# interface_visual.net
KiCad netlist of a schematic drawn in EAGLE
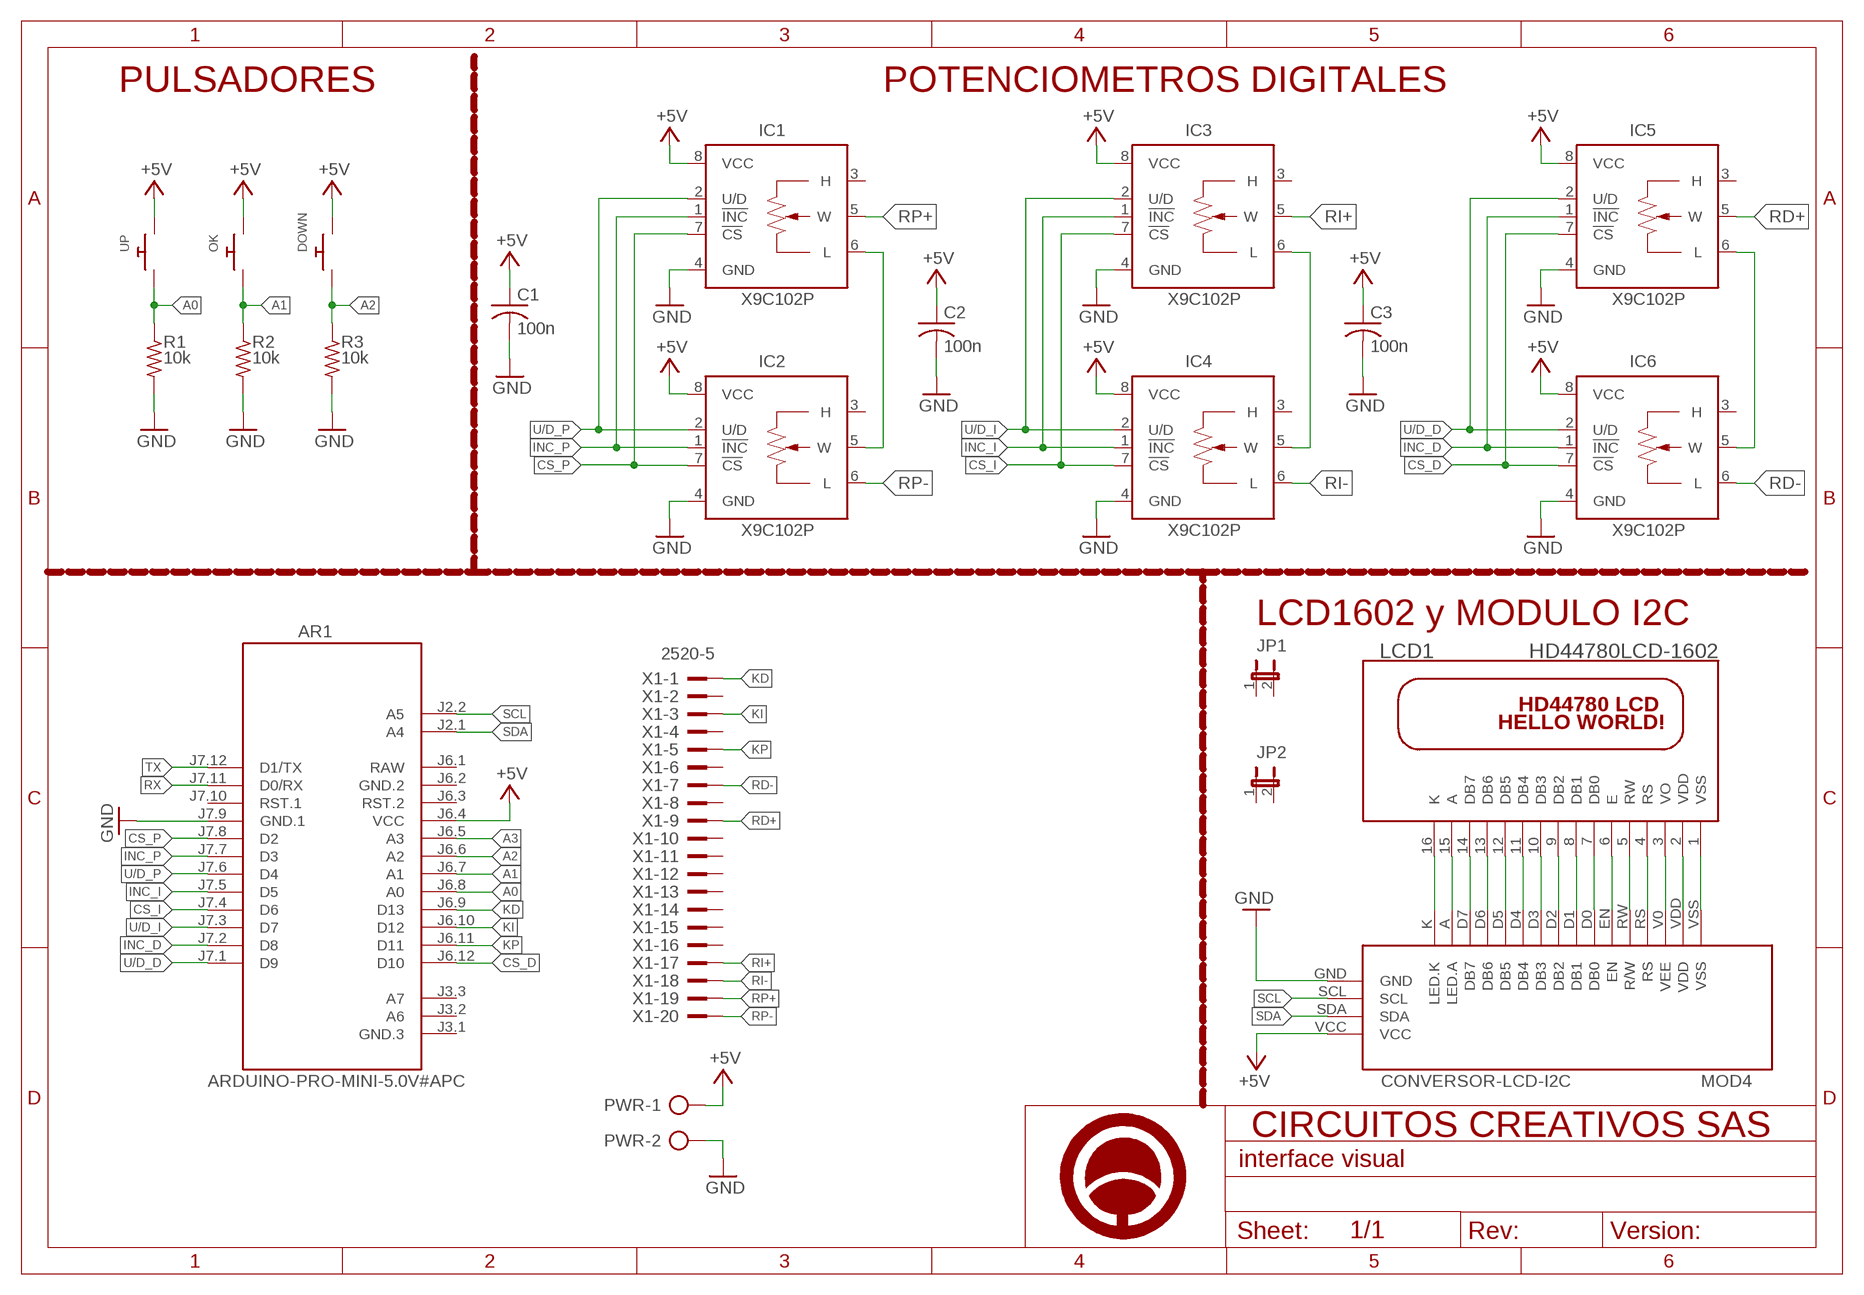
[diagram p0: schematic, sheet 1]

(export (version "E")
  (design (tool "Eeschema 10.0.6"))
  (components
    (comp (ref "AR1")
      (value "ARDUINO-PRO-MINI-5.0V#APC")
      (footprint "eagle-import:ARDUINO-PRO-MINI#APC")
      (libsource (lib "eagle-import") (part "ARDUINO-PRO-MINI-#APC5.0V"))
    )
    (comp (ref "C1")
      (value "100n")
      (footprint "eagle-import:C025-025X050")
      (libsource (lib "eagle-import") (part "C-US025-025X050"))
    )
    (comp (ref "C2")
      (value "100n")
      (footprint "eagle-import:C025-025X050")
      (libsource (lib "eagle-import") (part "C-US025-025X050"))
    )
    (comp (ref "C3")
      (value "100n")
      (footprint "eagle-import:C025-025X050")
      (libsource (lib "eagle-import") (part "C-US025-025X050"))
    )
    (comp (ref "DOWN")
      (value "SWITCH_PUSHBUTTONEVQ-PE")
      (footprint "eagle-import:TACT_PANA-EVQ")
      (libsource (lib "eagle-import") (part "SWITCH_PUSHBUTTONEVQ-PE"))
    )
    (comp (ref "IC1")
      (value "X9C102P")
      (footprint "eagle-import:DIL08")
      (fields (field (name "MF") "INTERSIL"))
      (libsource (lib "eagle-import") (part "X9C102P"))
    )
    (comp (ref "IC2")
      (value "X9C102P")
      (footprint "eagle-import:DIL08")
      (fields (field (name "MF") "INTERSIL"))
      (libsource (lib "eagle-import") (part "X9C102P"))
    )
    (comp (ref "IC3")
      (value "X9C102P")
      (footprint "eagle-import:DIL08")
      (fields (field (name "MF") "INTERSIL"))
      (libsource (lib "eagle-import") (part "X9C102P"))
    )
    (comp (ref "IC4")
      (value "X9C102P")
      (footprint "eagle-import:DIL08")
      (fields (field (name "MF") "INTERSIL"))
      (libsource (lib "eagle-import") (part "X9C102P"))
    )
    (comp (ref "IC5")
      (value "X9C102P")
      (footprint "eagle-import:DIL08")
      (fields (field (name "MF") "INTERSIL"))
      (libsource (lib "eagle-import") (part "X9C102P"))
    )
    (comp (ref "IC6")
      (value "X9C102P")
      (footprint "eagle-import:DIL08")
      (fields (field (name "MF") "INTERSIL"))
      (libsource (lib "eagle-import") (part "X9C102P"))
    )
    (comp (ref "JP1")
      (value "JP1E")
      (footprint "eagle-import:JP1")
      (libsource (lib "eagle-import") (part "JP1E"))
    )
    (comp (ref "JP2")
      (value "JP1E")
      (footprint "eagle-import:JP1")
      (libsource (lib "eagle-import") (part "JP1E"))
    )
    (comp (ref "LCD1")
      (value "HD44780LCD-1602")
      (footprint "eagle-import:LCD1602")
      (libsource (lib "eagle-import") (part "HD44780LCD-1602"))
    )
    (comp (ref "MOD4")
      (value "CONVERSOR-LCD-I2C")
      (footprint "eagle-import:CONVERSOR-LCD-I2C")
      (libsource (lib "eagle-import") (part "CONVERSOR-LCD-I2C"))
    )
    (comp (ref "OK")
      (value "SWITCH_PUSHBUTTONEVQ-PE")
      (footprint "eagle-import:TACT_PANA-EVQ")
      (libsource (lib "eagle-import") (part "SWITCH_PUSHBUTTONEVQ-PE"))
    )
    (comp (ref "PWR")
      (value "AK500/2")
      (footprint "eagle-import:AK500_2")
      (libsource (lib "eagle-import") (part "AK500/2"))
    )
    (comp (ref "R1")
      (value "10k")
      (footprint "eagle-import:0204_7")
      (libsource (lib "eagle-import") (part "R-US_0204/7"))
    )
    (comp (ref "R2")
      (value "10k")
      (footprint "eagle-import:0204_7")
      (libsource (lib "eagle-import") (part "R-US_0204/7"))
    )
    (comp (ref "R3")
      (value "10k")
      (footprint "eagle-import:0204_7")
      (libsource (lib "eagle-import") (part "R-US_0204/7"))
    )
    (comp (ref "U$1")
      (value "A4_HORIZONTAL")
      (footprint "eagle-import:LOGO")
      (libsource (lib "eagle-import") (part "A4_HORIZONTAL"))
    )
    (comp (ref "UP")
      (value "SWITCH_PUSHBUTTONEVQ-PE")
      (footprint "eagle-import:TACT_PANA-EVQ")
      (libsource (lib "eagle-import") (part "SWITCH_PUSHBUTTONEVQ-PE"))
    )
    (comp (ref "X1")
      (value "2520-5")
      (footprint "eagle-import:PAK100_2500-5-20")
      (fields (field (name "MPN") "D2520-5002-AR"))
      (libsource (lib "eagle-import") (part "2520-5"))
    )
  )
  (nets
    (net (code "1") (name "+5V") (class "Default")
      (node (ref "AR1") (pin "J6.4") (pinfunction "VCC_J6.4") (pintype "power_in"))
      (node (ref "C1") (pin "1") (pinfunction "1_1") (pintype "passive"))
      (node (ref "C2") (pin "1") (pinfunction "1_1") (pintype "passive"))
      (node (ref "C3") (pin "1") (pinfunction "1_1") (pintype "passive"))
      (node (ref "DOWN") (pin "P$2") (pinfunction "P$2_P$2") (pintype "passive"))
      (node (ref "IC1") (pin "8") (pinfunction "VCC_8") (pintype "power_in"))
      (node (ref "IC2") (pin "8") (pinfunction "VCC_8") (pintype "power_in"))
      (node (ref "IC3") (pin "8") (pinfunction "VCC_8") (pintype "power_in"))
      (node (ref "IC4") (pin "8") (pinfunction "VCC_8") (pintype "power_in"))
      (node (ref "IC5") (pin "8") (pinfunction "VCC_8") (pintype "power_in"))
      (node (ref "IC6") (pin "8") (pinfunction "VCC_8") (pintype "power_in"))
      (node (ref "MOD4") (pin "VCC") (pinfunction "VCC_VCC") (pintype "power_in"))
      (node (ref "OK") (pin "P$2") (pinfunction "P$2_P$2") (pintype "passive"))
      (node (ref "PWR") (pin "1") (pinfunction "KL_1") (pintype "passive"))
      (node (ref "UP") (pin "P$2") (pinfunction "P$2_P$2") (pintype "passive"))
    )
    (net (code "2") (name "/GND.2") (class "Default")
      (node (ref "AR1") (pin "J6.2") (pinfunction "GND.2_J6.2") (pintype "power_in"))
    )
    (net (code "3") (name "/RAW") (class "Default")
      (node (ref "AR1") (pin "J6.1") (pinfunction "RAW_J6.1") (pintype "power_in"))
    )
    (net (code "4") (name "A0") (class "Default")
      (node (ref "AR1") (pin "J6.8") (pinfunction "A0_J6.8") (pintype "bidirectional"))
      (node (ref "R1") (pin "1") (pinfunction "1_1") (pintype "passive"))
      (node (ref "UP") (pin "P$1") (pinfunction "P$1_P$1") (pintype "passive"))
    )
    (net (code "5") (name "A1") (class "Default")
      (node (ref "AR1") (pin "J6.7") (pinfunction "A1_J6.7") (pintype "bidirectional"))
      (node (ref "OK") (pin "P$1") (pinfunction "P$1_P$1") (pintype "passive"))
      (node (ref "R2") (pin "1") (pinfunction "1_1") (pintype "passive"))
    )
    (net (code "6") (name "A2") (class "Default")
      (node (ref "AR1") (pin "J6.6") (pinfunction "A2_J6.6") (pintype "bidirectional"))
      (node (ref "DOWN") (pin "P$1") (pinfunction "P$1_P$1") (pintype "passive"))
      (node (ref "R3") (pin "1") (pinfunction "1_1") (pintype "passive"))
    )
    (net (code "7") (name "A3") (class "Default")
      (node (ref "AR1") (pin "J6.5") (pinfunction "A3_J6.5") (pintype "bidirectional"))
    )
    (net (code "8") (name "CS_D") (class "Default")
      (node (ref "AR1") (pin "J6.12") (pinfunction "D10_J6.12") (pintype "bidirectional"))
      (node (ref "IC5") (pin "7") (pinfunction "~{CS}_7") (pintype "input"))
      (node (ref "IC6") (pin "7") (pinfunction "~{CS}_7") (pintype "input"))
    )
    (net (code "9") (name "CS_I") (class "Default")
      (node (ref "AR1") (pin "J7.4") (pinfunction "D6_J7.4") (pintype "bidirectional"))
      (node (ref "IC3") (pin "7") (pinfunction "~{CS}_7") (pintype "input"))
      (node (ref "IC4") (pin "7") (pinfunction "~{CS}_7") (pintype "input"))
    )
    (net (code "10") (name "CS_P") (class "Default")
      (node (ref "AR1") (pin "J7.8") (pinfunction "D2_J7.8") (pintype "bidirectional"))
      (node (ref "IC1") (pin "7") (pinfunction "~{CS}_7") (pintype "input"))
      (node (ref "IC2") (pin "7") (pinfunction "~{CS}_7") (pintype "input"))
    )
    (net (code "11") (name "GND") (class "Default")
      (node (ref "AR1") (pin "J7.9") (pinfunction "GND.1_J7.9") (pintype "power_in"))
      (node (ref "C1") (pin "2") (pinfunction "2_2") (pintype "passive"))
      (node (ref "C2") (pin "2") (pinfunction "2_2") (pintype "passive"))
      (node (ref "C3") (pin "2") (pinfunction "2_2") (pintype "passive"))
      (node (ref "IC1") (pin "4") (pinfunction "GND_4") (pintype "power_in"))
      (node (ref "IC2") (pin "4") (pinfunction "GND_4") (pintype "power_in"))
      (node (ref "IC3") (pin "4") (pinfunction "GND_4") (pintype "power_in"))
      (node (ref "IC4") (pin "4") (pinfunction "GND_4") (pintype "power_in"))
      (node (ref "IC5") (pin "4") (pinfunction "GND_4") (pintype "power_in"))
      (node (ref "IC6") (pin "4") (pinfunction "GND_4") (pintype "power_in"))
      (node (ref "MOD4") (pin "GND") (pinfunction "GND_GND") (pintype "power_in"))
      (node (ref "PWR") (pin "2") (pinfunction "KL_2") (pintype "passive"))
      (node (ref "R1") (pin "2") (pinfunction "2_2") (pintype "passive"))
      (node (ref "R2") (pin "2") (pinfunction "2_2") (pintype "passive"))
      (node (ref "R3") (pin "2") (pinfunction "2_2") (pintype "passive"))
    )
    (net (code "12") (name "INC_D") (class "Default")
      (node (ref "AR1") (pin "J7.2") (pinfunction "D8_J7.2") (pintype "bidirectional"))
      (node (ref "IC5") (pin "1") (pinfunction "~{INC}_1") (pintype "input"))
      (node (ref "IC6") (pin "1") (pinfunction "~{INC}_1") (pintype "input"))
    )
    (net (code "13") (name "INC_I") (class "Default")
      (node (ref "AR1") (pin "J7.5") (pinfunction "D5_J7.5") (pintype "bidirectional"))
      (node (ref "IC3") (pin "1") (pinfunction "~{INC}_1") (pintype "input"))
      (node (ref "IC4") (pin "1") (pinfunction "~{INC}_1") (pintype "input"))
    )
    (net (code "14") (name "INC_P") (class "Default")
      (node (ref "AR1") (pin "J7.7") (pinfunction "D3_J7.7") (pintype "bidirectional"))
      (node (ref "IC1") (pin "1") (pinfunction "~{INC}_1") (pintype "input"))
      (node (ref "IC2") (pin "1") (pinfunction "~{INC}_1") (pintype "input"))
    )
    (net (code "15") (name "KD") (class "Default")
      (node (ref "AR1") (pin "J6.9") (pinfunction "D13_J6.9") (pintype "bidirectional"))
      (node (ref "X1") (pin "1") (pinfunction "KL_1") (pintype "passive"))
    )
    (net (code "16") (name "KI") (class "Default")
      (node (ref "AR1") (pin "J6.10") (pinfunction "D12_J6.10") (pintype "bidirectional"))
      (node (ref "X1") (pin "3") (pinfunction "KL_3") (pintype "passive"))
    )
    (net (code "17") (name "KP") (class "Default")
      (node (ref "AR1") (pin "J6.11") (pinfunction "D11_J6.11") (pintype "bidirectional"))
      (node (ref "X1") (pin "5") (pinfunction "KL_5") (pintype "passive"))
    )
    (net (code "18") (name "Net-(IC1-L)") (class "Default")
      (node (ref "IC1") (pin "6") (pinfunction "L_6") (pintype "passive"))
      (node (ref "IC2") (pin "5") (pinfunction "W_5") (pintype "passive"))
    )
    (net (code "19") (name "Net-(IC3-L)") (class "Default")
      (node (ref "IC3") (pin "6") (pinfunction "L_6") (pintype "passive"))
      (node (ref "IC4") (pin "5") (pinfunction "W_5") (pintype "passive"))
    )
    (net (code "20") (name "Net-(IC5-L)") (class "Default")
      (node (ref "IC5") (pin "6") (pinfunction "L_6") (pintype "passive"))
      (node (ref "IC6") (pin "5") (pinfunction "W_5") (pintype "passive"))
    )
    (net (code "21") (name "Net-(LCD1-A)") (class "Default")
      (node (ref "LCD1") (pin "15") (pinfunction "A_15") (pintype "input"))
      (node (ref "MOD4") (pin "A") (pinfunction "LED.A_A") (pintype "bidirectional"))
    )
    (net (code "22") (name "Net-(LCD1-DB0)") (class "Default")
      (node (ref "LCD1") (pin "7") (pinfunction "DB0_7") (pintype "bidirectional"))
      (node (ref "MOD4") (pin "D0") (pinfunction "DB0_D0") (pintype "bidirectional"))
    )
    (net (code "23") (name "Net-(LCD1-DB1)") (class "Default")
      (node (ref "LCD1") (pin "8") (pinfunction "DB1_8") (pintype "bidirectional"))
      (node (ref "MOD4") (pin "D1") (pinfunction "DB1_D1") (pintype "bidirectional"))
    )
    (net (code "24") (name "Net-(LCD1-DB2)") (class "Default")
      (node (ref "LCD1") (pin "9") (pinfunction "DB2_9") (pintype "bidirectional"))
      (node (ref "MOD4") (pin "D2") (pinfunction "DB2_D2") (pintype "bidirectional"))
    )
    (net (code "25") (name "Net-(LCD1-DB3)") (class "Default")
      (node (ref "LCD1") (pin "10") (pinfunction "DB3_10") (pintype "bidirectional"))
      (node (ref "MOD4") (pin "D3") (pinfunction "DB3_D3") (pintype "bidirectional"))
    )
    (net (code "26") (name "Net-(LCD1-DB4)") (class "Default")
      (node (ref "LCD1") (pin "11") (pinfunction "DB4_11") (pintype "bidirectional"))
      (node (ref "MOD4") (pin "D4") (pinfunction "DB4_D4") (pintype "bidirectional"))
    )
    (net (code "27") (name "Net-(LCD1-DB5)") (class "Default")
      (node (ref "LCD1") (pin "12") (pinfunction "DB5_12") (pintype "bidirectional"))
      (node (ref "MOD4") (pin "D5") (pinfunction "DB5_D5") (pintype "bidirectional"))
    )
    (net (code "28") (name "Net-(LCD1-DB6)") (class "Default")
      (node (ref "LCD1") (pin "13") (pinfunction "DB6_13") (pintype "bidirectional"))
      (node (ref "MOD4") (pin "D6") (pinfunction "DB6_D6") (pintype "bidirectional"))
    )
    (net (code "29") (name "Net-(LCD1-DB7)") (class "Default")
      (node (ref "LCD1") (pin "14") (pinfunction "DB7_14") (pintype "bidirectional"))
      (node (ref "MOD4") (pin "D7") (pinfunction "DB7_D7") (pintype "bidirectional"))
    )
    (net (code "30") (name "Net-(LCD1-E)") (class "Default")
      (node (ref "LCD1") (pin "6") (pinfunction "E_6") (pintype "input"))
      (node (ref "MOD4") (pin "EN") (pinfunction "EN_EN") (pintype "bidirectional"))
    )
    (net (code "31") (name "Net-(LCD1-K)") (class "Default")
      (node (ref "LCD1") (pin "16") (pinfunction "K_16") (pintype "input"))
      (node (ref "MOD4") (pin "K") (pinfunction "LED.K_K") (pintype "bidirectional"))
    )
    (net (code "32") (name "Net-(LCD1-RS)") (class "Default")
      (node (ref "LCD1") (pin "4") (pinfunction "RS_4") (pintype "input"))
      (node (ref "MOD4") (pin "RS") (pinfunction "RS_RS") (pintype "bidirectional"))
    )
    (net (code "33") (name "Net-(LCD1-RW)") (class "Default")
      (node (ref "LCD1") (pin "5") (pinfunction "RW_5") (pintype "input"))
      (node (ref "MOD4") (pin "RW") (pinfunction "R/W_RW") (pintype "bidirectional"))
    )
    (net (code "34") (name "Net-(LCD1-VDD)") (class "Default")
      (node (ref "LCD1") (pin "2") (pinfunction "VDD_2") (pintype "power_in"))
      (node (ref "MOD4") (pin "VDD") (pinfunction "VDD_VDD") (pintype "bidirectional"))
    )
    (net (code "35") (name "Net-(LCD1-VO)") (class "Default")
      (node (ref "LCD1") (pin "3") (pinfunction "VO_3") (pintype "input"))
      (node (ref "MOD4") (pin "V0") (pinfunction "VEE_V0") (pintype "bidirectional"))
    )
    (net (code "36") (name "Net-(LCD1-VSS)") (class "Default")
      (node (ref "LCD1") (pin "1") (pinfunction "VSS_1") (pintype "power_in"))
      (node (ref "MOD4") (pin "VSS") (pinfunction "VSS_VSS") (pintype "bidirectional"))
    )
    (net (code "37") (name "RD+") (class "Default")
      (node (ref "IC5") (pin "5") (pinfunction "W_5") (pintype "passive"))
      (node (ref "X1") (pin "9") (pinfunction "KL_9") (pintype "passive"))
    )
    (net (code "38") (name "RD-") (class "Default")
      (node (ref "IC6") (pin "6") (pinfunction "L_6") (pintype "passive"))
      (node (ref "X1") (pin "7") (pinfunction "KL_7") (pintype "passive"))
    )
    (net (code "39") (name "RI+") (class "Default")
      (node (ref "IC3") (pin "5") (pinfunction "W_5") (pintype "passive"))
      (node (ref "X1") (pin "17") (pinfunction "KL_17") (pintype "passive"))
    )
    (net (code "40") (name "RI-") (class "Default")
      (node (ref "IC4") (pin "6") (pinfunction "L_6") (pintype "passive"))
      (node (ref "X1") (pin "18") (pinfunction "KL_18") (pintype "passive"))
    )
    (net (code "41") (name "RP+") (class "Default")
      (node (ref "IC1") (pin "5") (pinfunction "W_5") (pintype "passive"))
      (node (ref "X1") (pin "19") (pinfunction "KL_19") (pintype "passive"))
    )
    (net (code "42") (name "RP-") (class "Default")
      (node (ref "IC2") (pin "6") (pinfunction "L_6") (pintype "passive"))
      (node (ref "X1") (pin "20") (pinfunction "KL_20") (pintype "passive"))
    )
    (net (code "43") (name "RX") (class "Default")
      (node (ref "AR1") (pin "J7.11") (pinfunction "D0/RX_J7.11") (pintype "bidirectional"))
    )
    (net (code "44") (name "SCL") (class "Default")
      (node (ref "AR1") (pin "J2.2") (pinfunction "A5_J2.2") (pintype "bidirectional"))
      (node (ref "MOD4") (pin "SCL") (pinfunction "SCL_SCL") (pintype "bidirectional"))
    )
    (net (code "45") (name "SDA") (class "Default")
      (node (ref "AR1") (pin "J2.1") (pinfunction "A4_J2.1") (pintype "bidirectional"))
      (node (ref "MOD4") (pin "SDA") (pinfunction "SDA_SDA") (pintype "bidirectional"))
    )
    (net (code "46") (name "TX") (class "Default")
      (node (ref "AR1") (pin "J7.12") (pinfunction "D1/TX_J7.12") (pintype "bidirectional"))
    )
    (net (code "47") (name "U{slash}D_D") (class "Default")
      (node (ref "AR1") (pin "J7.1") (pinfunction "D9_J7.1") (pintype "bidirectional"))
      (node (ref "IC5") (pin "2") (pinfunction "U/D_2") (pintype "input"))
      (node (ref "IC6") (pin "2") (pinfunction "U/D_2") (pintype "input"))
    )
    (net (code "48") (name "U{slash}D_I") (class "Default")
      (node (ref "AR1") (pin "J7.3") (pinfunction "D7_J7.3") (pintype "bidirectional"))
      (node (ref "IC3") (pin "2") (pinfunction "U/D_2") (pintype "input"))
      (node (ref "IC4") (pin "2") (pinfunction "U/D_2") (pintype "input"))
    )
    (net (code "49") (name "U{slash}D_P") (class "Default")
      (node (ref "AR1") (pin "J7.6") (pinfunction "D4_J7.6") (pintype "bidirectional"))
      (node (ref "IC1") (pin "2") (pinfunction "U/D_2") (pintype "input"))
      (node (ref "IC2") (pin "2") (pinfunction "U/D_2") (pintype "input"))
    )
    (net (code "50") (name "unconnected-(AR1-A6-PadJ3.2)") (class "Default")
      (node (ref "AR1") (pin "J3.2") (pinfunction "A6_J3.2") (pintype "bidirectional"))
    )
    (net (code "51") (name "unconnected-(AR1-A7-PadJ3.3)") (class "Default")
      (node (ref "AR1") (pin "J3.3") (pinfunction "A7_J3.3") (pintype "bidirectional"))
    )
    (net (code "52") (name "unconnected-(AR1-GND.3-PadJ3.1)") (class "Default")
      (node (ref "AR1") (pin "J3.1") (pinfunction "GND.3_J3.1") (pintype "bidirectional"))
    )
    (net (code "53") (name "unconnected-(AR1-RST.1-PadJ7.10)") (class "Default")
      (node (ref "AR1") (pin "J7.10") (pinfunction "RST.1_J7.10") (pintype "bidirectional"))
    )
    (net (code "54") (name "unconnected-(AR1-RST.2-PadJ6.3)") (class "Default")
      (node (ref "AR1") (pin "J6.3") (pinfunction "RST.2_J6.3") (pintype "bidirectional"))
    )
    (net (code "55") (name "unconnected-(IC1-H-Pad3)") (class "Default")
      (node (ref "IC1") (pin "3") (pinfunction "H_3") (pintype "passive"))
    )
    (net (code "56") (name "unconnected-(IC2-H-Pad3)") (class "Default")
      (node (ref "IC2") (pin "3") (pinfunction "H_3") (pintype "passive"))
    )
    (net (code "57") (name "unconnected-(IC3-H-Pad3)") (class "Default")
      (node (ref "IC3") (pin "3") (pinfunction "H_3") (pintype "passive"))
    )
    (net (code "58") (name "unconnected-(IC4-H-Pad3)") (class "Default")
      (node (ref "IC4") (pin "3") (pinfunction "H_3") (pintype "passive"))
    )
    (net (code "59") (name "unconnected-(IC5-H-Pad3)") (class "Default")
      (node (ref "IC5") (pin "3") (pinfunction "H_3") (pintype "passive"))
    )
    (net (code "60") (name "unconnected-(IC6-H-Pad3)") (class "Default")
      (node (ref "IC6") (pin "3") (pinfunction "H_3") (pintype "passive"))
    )
    (net (code "61") (name "unconnected-(JP1-Pad1)") (class "Default")
      (node (ref "JP1") (pin "1") (pinfunction "1_1") (pintype "passive"))
    )
    (net (code "62") (name "unconnected-(JP1-Pad2)") (class "Default")
      (node (ref "JP1") (pin "2") (pinfunction "2_2") (pintype "passive"))
    )
    (net (code "63") (name "unconnected-(JP2-Pad1)") (class "Default")
      (node (ref "JP2") (pin "1") (pinfunction "1_1") (pintype "passive"))
    )
    (net (code "64") (name "unconnected-(JP2-Pad2)") (class "Default")
      (node (ref "JP2") (pin "2") (pinfunction "2_2") (pintype "passive"))
    )
    (net (code "65") (name "unconnected-(X1B-KL-Pad10)") (class "Default")
      (node (ref "X1") (pin "10") (pinfunction "KL_10") (pintype "passive"))
    )
    (net (code "66") (name "unconnected-(X1C-KL-Pad11)") (class "Default")
      (node (ref "X1") (pin "11") (pinfunction "KL_11") (pintype "passive"))
    )
    (net (code "67") (name "unconnected-(X1D-KL-Pad12)") (class "Default")
      (node (ref "X1") (pin "12") (pinfunction "KL_12") (pintype "passive"))
    )
    (net (code "68") (name "unconnected-(X1E-KL-Pad13)") (class "Default")
      (node (ref "X1") (pin "13") (pinfunction "KL_13") (pintype "passive"))
    )
    (net (code "69") (name "unconnected-(X1F-KL-Pad14)") (class "Default")
      (node (ref "X1") (pin "14") (pinfunction "KL_14") (pintype "passive"))
    )
    (net (code "70") (name "unconnected-(X1G-KL-Pad15)") (class "Default")
      (node (ref "X1") (pin "15") (pinfunction "KL_15") (pintype "passive"))
    )
    (net (code "71") (name "unconnected-(X1H-KL-Pad16)") (class "Default")
      (node (ref "X1") (pin "16") (pinfunction "KL_16") (pintype "passive"))
    )
    (net (code "72") (name "unconnected-(X1L-KL-Pad2)") (class "Default")
      (node (ref "X1") (pin "2") (pinfunction "KL_2") (pintype "passive"))
    )
    (net (code "73") (name "unconnected-(X1O-KL-Pad4)") (class "Default")
      (node (ref "X1") (pin "4") (pinfunction "KL_4") (pintype "passive"))
    )
    (net (code "74") (name "unconnected-(X1Q-KL-Pad6)") (class "Default")
      (node (ref "X1") (pin "6") (pinfunction "KL_6") (pintype "passive"))
    )
    (net (code "75") (name "unconnected-(X1S-KL-Pad8)") (class "Default")
      (node (ref "X1") (pin "8") (pinfunction "KL_8") (pintype "passive"))
    )
  )
)
